# jiffy-neoram-smd.net
KiCad netlist of a schematic drawn in EAGLE
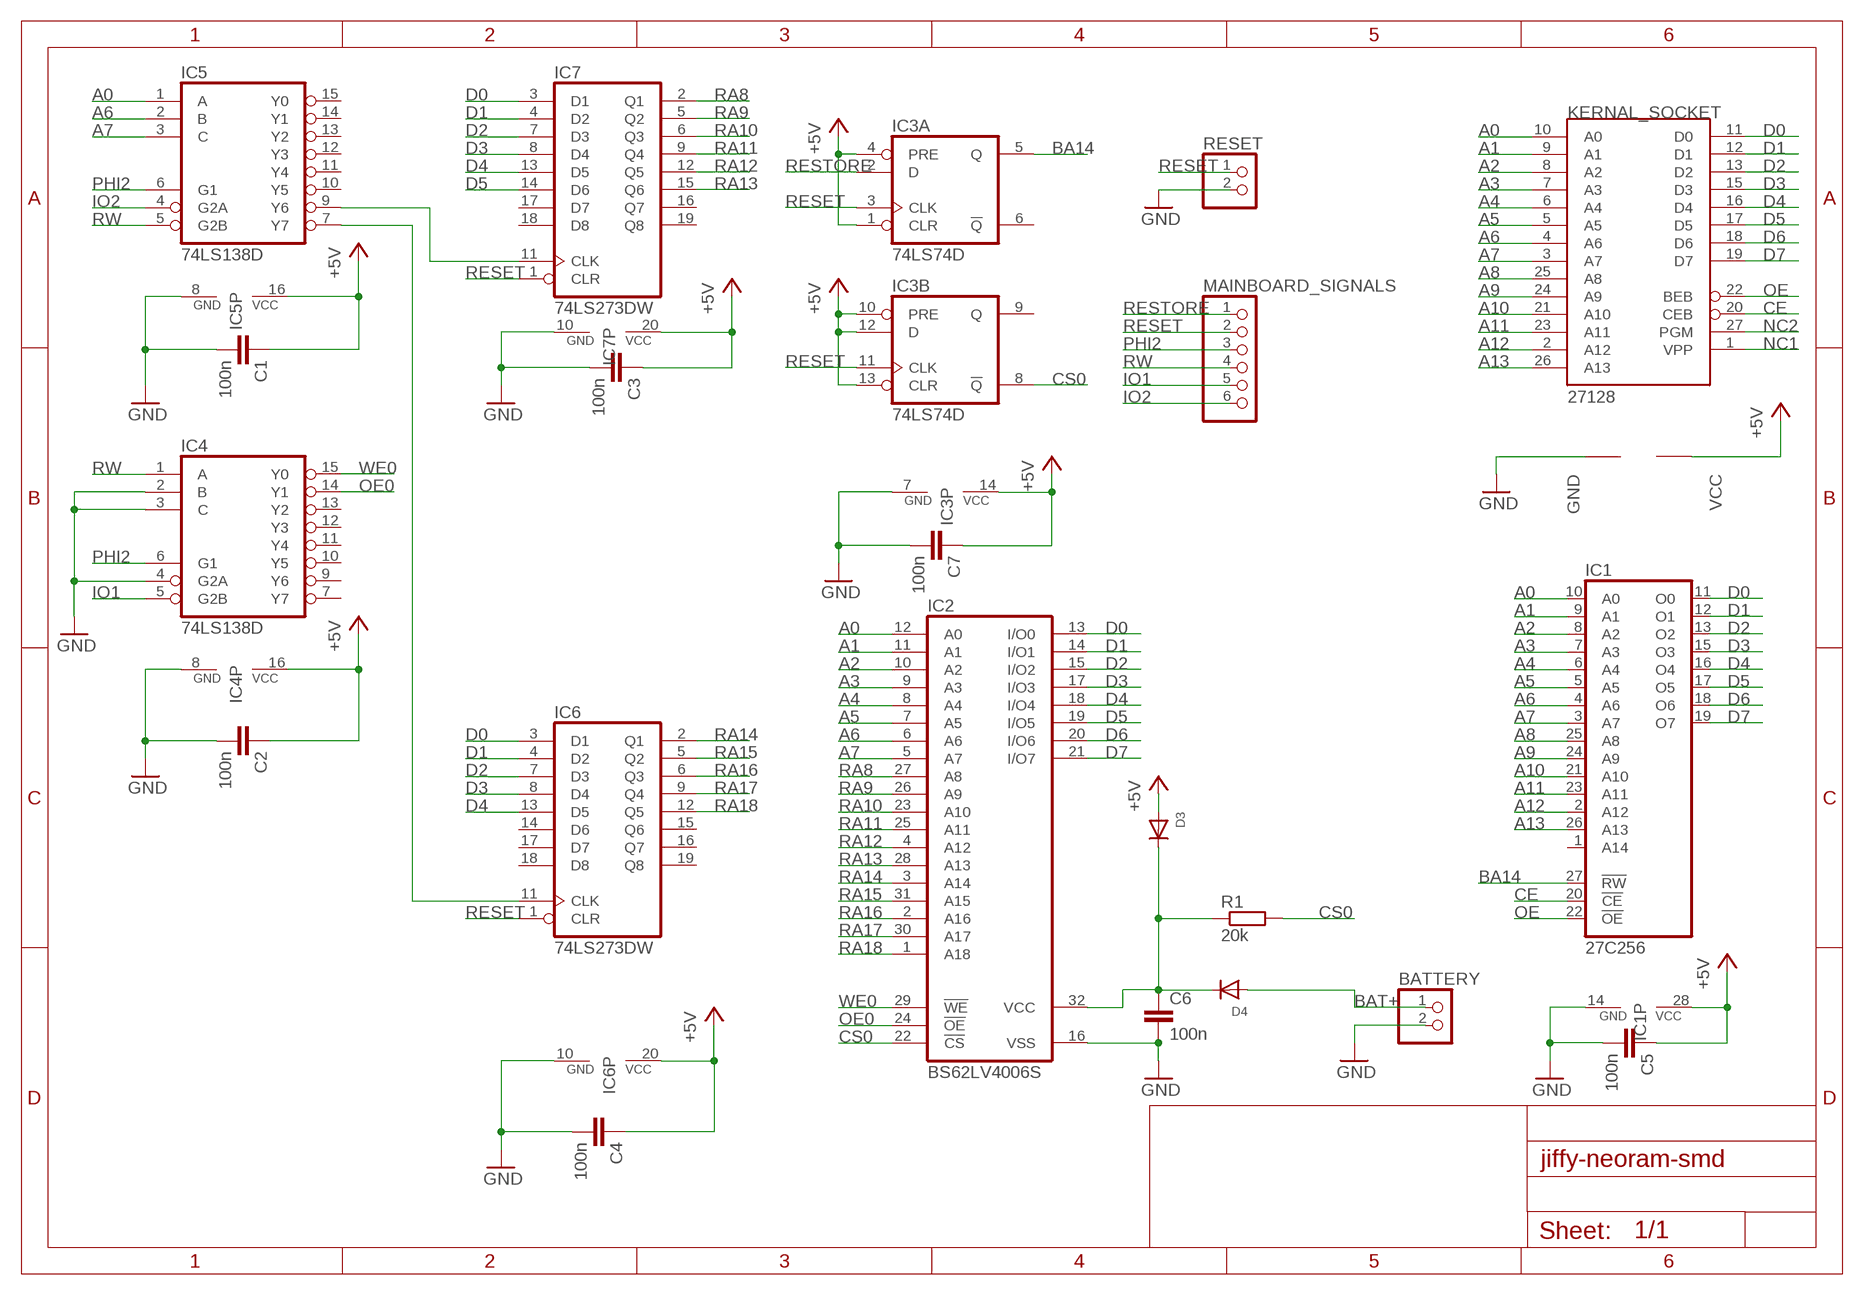
[diagram p0: schematic, sheet 1]

(export (version "E")
  (design (tool "Eeschema 10.0.6"))
  (components
    (comp (ref "BATTERY")
      (value "HEADER-1X2ROUND")
      (footprint "eagle-import:1X02_ROUND")
      (libsource (lib "eagle-import") (part "HEADER-1X2ROUND"))
    )
    (comp (ref "C1")
      (value "100n")
      (footprint "eagle-import:C0603")
      (libsource (lib "eagle-import") (part "C-EUC0603"))
    )
    (comp (ref "C2")
      (value "100n")
      (footprint "eagle-import:C0603")
      (libsource (lib "eagle-import") (part "C-EUC0603"))
    )
    (comp (ref "C3")
      (value "100n")
      (footprint "eagle-import:C0603")
      (libsource (lib "eagle-import") (part "C-EUC0603"))
    )
    (comp (ref "C4")
      (value "100n")
      (footprint "eagle-import:C0603")
      (libsource (lib "eagle-import") (part "C-EUC0603"))
    )
    (comp (ref "C5")
      (value "100n")
      (footprint "eagle-import:C0603")
      (libsource (lib "eagle-import") (part "C-EUC0603"))
    )
    (comp (ref "C6")
      (value "100n")
      (footprint "eagle-import:C0603")
      (libsource (lib "eagle-import") (part "C-EUC0603"))
    )
    (comp (ref "C7")
      (value "100n")
      (footprint "eagle-import:C0603")
      (libsource (lib "eagle-import") (part "C-EUC0603"))
    )
    (comp (ref "D3")
      (value "DIODESOD-323F")
      (footprint "eagle-import:SOD-323F")
      (libsource (lib "eagle-import") (part "DIODESOD-323F"))
    )
    (comp (ref "D4")
      (value "DIODESOD-323F")
      (footprint "eagle-import:SOD-323F")
      (libsource (lib "eagle-import") (part "DIODESOD-323F"))
    )
    (comp (ref "IC1")
      (value "27C256")
      (footprint "eagle-import:DIL28")
      (libsource (lib "eagle-import") (part "TC55257DP"))
    )
    (comp (ref "IC2")
      (value "BS62LV4006S")
      (footprint "eagle-import:SOP-32")
      (libsource (lib "eagle-import") (part "BS62LV4006S"))
    )
    (comp (ref "IC3")
      (value "74LS74D")
      (footprint "eagle-import:SO14")
      (libsource (lib "eagle-import") (part "7474DLS"))
    )
    (comp (ref "IC4")
      (value "74LS138D")
      (footprint "eagle-import:SO16")
      (libsource (lib "eagle-import") (part "74138DLS"))
    )
    (comp (ref "IC5")
      (value "74LS138D")
      (footprint "eagle-import:SO16")
      (libsource (lib "eagle-import") (part "74138DLS"))
    )
    (comp (ref "IC6")
      (value "74LS273DW")
      (footprint "eagle-import:SO20W")
      (libsource (lib "eagle-import") (part "74273DWLS"))
    )
    (comp (ref "IC7")
      (value "74LS273DW")
      (footprint "eagle-import:SO20W")
      (libsource (lib "eagle-import") (part "74273DWLS"))
    )
    (comp (ref "KERNAL_SOCKET")
      (value "OSROM")
      (footprint "eagle-import:DIL28-6")
      (libsource (lib "eagle-import") (part "OSROM"))
    )
    (comp (ref "MAINBOARD_SIGNALS")
      (value "HEADER-1X6ROUND")
      (footprint "eagle-import:1X06_ROUND")
      (libsource (lib "eagle-import") (part "HEADER-1X6ROUND"))
    )
    (comp (ref "R1")
      (value "20k")
      (footprint "eagle-import:R0603")
      (libsource (lib "eagle-import") (part "R-EU_R0603"))
    )
    (comp (ref "RESET")
      (value "HEADER-1X2ROUND")
      (footprint "eagle-import:1X02_ROUND")
      (libsource (lib "eagle-import") (part "HEADER-1X2ROUND"))
    )
  )
  (nets
    (net (code "1") (name "+5V") (class "Default")
      (node (ref "C1") (pin "1") (pinfunction "1_1") (pintype "passive"))
      (node (ref "C2") (pin "1") (pinfunction "1_1") (pintype "passive"))
      (node (ref "C3") (pin "1") (pinfunction "1_1") (pintype "passive"))
      (node (ref "C4") (pin "1") (pinfunction "1_1") (pintype "passive"))
      (node (ref "C5") (pin "1") (pinfunction "1_1") (pintype "passive"))
      (node (ref "C7") (pin "1") (pinfunction "1_1") (pintype "passive"))
      (node (ref "D3") (pin "A") (pinfunction "A_A") (pintype "passive"))
      (node (ref "IC1") (pin "28") (pinfunction "VCC_28") (pintype "power_in"))
      (node (ref "IC3") (pin "1") (pinfunction "CLR_1") (pintype "input"))
      (node (ref "IC3") (pin "10") (pinfunction "PRE_10") (pintype "input"))
      (node (ref "IC3") (pin "12") (pinfunction "D_12") (pintype "input"))
      (node (ref "IC3") (pin "13") (pinfunction "CLR_13") (pintype "input"))
      (node (ref "IC3") (pin "14") (pinfunction "VCC_14") (pintype "power_in"))
      (node (ref "IC3") (pin "4") (pinfunction "PRE_4") (pintype "input"))
      (node (ref "IC4") (pin "16") (pinfunction "VCC_16") (pintype "power_in"))
      (node (ref "IC5") (pin "16") (pinfunction "VCC_16") (pintype "power_in"))
      (node (ref "IC6") (pin "20") (pinfunction "VCC_20") (pintype "power_in"))
      (node (ref "IC7") (pin "20") (pinfunction "VCC_20") (pintype "power_in"))
      (node (ref "KERNAL_SOCKET") (pin "28") (pinfunction "VCC_28") (pintype "power_in"))
    )
    (net (code "2") (name "/A0") (class "Default")
      (node (ref "IC1") (pin "10") (pinfunction "A0_10") (pintype "input"))
      (node (ref "IC2") (pin "12") (pinfunction "A0_12") (pintype "input"))
      (node (ref "IC5") (pin "1") (pinfunction "A_1") (pintype "input"))
      (node (ref "KERNAL_SOCKET") (pin "10") (pinfunction "A0_10") (pintype "input"))
    )
    (net (code "3") (name "/A1") (class "Default")
      (node (ref "IC1") (pin "9") (pinfunction "A1_9") (pintype "input"))
      (node (ref "IC2") (pin "11") (pinfunction "A1_11") (pintype "input"))
      (node (ref "KERNAL_SOCKET") (pin "9") (pinfunction "A1_9") (pintype "input"))
    )
    (net (code "4") (name "/A2") (class "Default")
      (node (ref "IC1") (pin "8") (pinfunction "A2_8") (pintype "input"))
      (node (ref "IC2") (pin "10") (pinfunction "A2_10") (pintype "input"))
      (node (ref "KERNAL_SOCKET") (pin "8") (pinfunction "A2_8") (pintype "input"))
    )
    (net (code "5") (name "/A3") (class "Default")
      (node (ref "IC1") (pin "7") (pinfunction "A3_7") (pintype "input"))
      (node (ref "IC2") (pin "9") (pinfunction "A3_9") (pintype "input"))
      (node (ref "KERNAL_SOCKET") (pin "7") (pinfunction "A3_7") (pintype "input"))
    )
    (net (code "6") (name "/A4") (class "Default")
      (node (ref "IC1") (pin "6") (pinfunction "A4_6") (pintype "input"))
      (node (ref "IC2") (pin "8") (pinfunction "A4_8") (pintype "input"))
      (node (ref "KERNAL_SOCKET") (pin "6") (pinfunction "A4_6") (pintype "input"))
    )
    (net (code "7") (name "/A5") (class "Default")
      (node (ref "IC1") (pin "5") (pinfunction "A5_5") (pintype "input"))
      (node (ref "IC2") (pin "7") (pinfunction "A5_7") (pintype "input"))
      (node (ref "KERNAL_SOCKET") (pin "5") (pinfunction "A5_5") (pintype "input"))
    )
    (net (code "8") (name "/A6") (class "Default")
      (node (ref "IC1") (pin "4") (pinfunction "A6_4") (pintype "input"))
      (node (ref "IC2") (pin "6") (pinfunction "A6_6") (pintype "input"))
      (node (ref "IC5") (pin "2") (pinfunction "B_2") (pintype "input"))
      (node (ref "KERNAL_SOCKET") (pin "4") (pinfunction "A6_4") (pintype "input"))
    )
    (net (code "9") (name "/A7") (class "Default")
      (node (ref "IC1") (pin "3") (pinfunction "A7_3") (pintype "input"))
      (node (ref "IC2") (pin "5") (pinfunction "A7_5") (pintype "input"))
      (node (ref "IC5") (pin "3") (pinfunction "C_3") (pintype "input"))
      (node (ref "KERNAL_SOCKET") (pin "3") (pinfunction "A7_3") (pintype "input"))
    )
    (net (code "10") (name "/A8") (class "Default")
      (node (ref "IC1") (pin "25") (pinfunction "A8_25") (pintype "input"))
      (node (ref "KERNAL_SOCKET") (pin "25") (pinfunction "A8_25") (pintype "input"))
    )
    (net (code "11") (name "/A9") (class "Default")
      (node (ref "IC1") (pin "24") (pinfunction "A9_24") (pintype "input"))
      (node (ref "KERNAL_SOCKET") (pin "24") (pinfunction "A9_24") (pintype "input"))
    )
    (net (code "12") (name "/A10") (class "Default")
      (node (ref "IC1") (pin "21") (pinfunction "A10_21") (pintype "input"))
      (node (ref "KERNAL_SOCKET") (pin "21") (pinfunction "A10_21") (pintype "input"))
    )
    (net (code "13") (name "/A11") (class "Default")
      (node (ref "IC1") (pin "23") (pinfunction "A11_23") (pintype "input"))
      (node (ref "KERNAL_SOCKET") (pin "23") (pinfunction "A11_23") (pintype "input"))
    )
    (net (code "14") (name "/A12") (class "Default")
      (node (ref "IC1") (pin "2") (pinfunction "A12_2") (pintype "input"))
      (node (ref "KERNAL_SOCKET") (pin "2") (pinfunction "A12_2") (pintype "input"))
    )
    (net (code "15") (name "/A13") (class "Default")
      (node (ref "IC1") (pin "26") (pinfunction "A13_26") (pintype "input"))
      (node (ref "KERNAL_SOCKET") (pin "26") (pinfunction "A13_26") (pintype "input"))
    )
    (net (code "16") (name "/BA14") (class "Default")
      (node (ref "IC1") (pin "27") (pinfunction "~{RW}_27") (pintype "input"))
      (node (ref "IC3") (pin "5") (pinfunction "Q_5") (pintype "output"))
    )
    (net (code "17") (name "/BAT+") (class "Default")
      (node (ref "BATTERY") (pin "1") (pinfunction "1_1") (pintype "passive"))
      (node (ref "D4") (pin "A") (pinfunction "A_A") (pintype "passive"))
    )
    (net (code "18") (name "/CE") (class "Default")
      (node (ref "IC1") (pin "20") (pinfunction "~{CE}_20") (pintype "input"))
      (node (ref "KERNAL_SOCKET") (pin "20") (pinfunction "CEB_20") (pintype "input"))
    )
    (net (code "19") (name "/CS0") (class "Default")
      (node (ref "IC2") (pin "22") (pinfunction "~{CS}_22") (pintype "input"))
      (node (ref "IC3") (pin "8") (pinfunction "~{Q}_8") (pintype "output"))
      (node (ref "R1") (pin "2") (pinfunction "2_2") (pintype "passive"))
    )
    (net (code "20") (name "/D0") (class "Default")
      (node (ref "IC1") (pin "11") (pinfunction "O0_11") (pintype "tri_state"))
      (node (ref "IC2") (pin "13") (pinfunction "I/O0_13") (pintype "bidirectional"))
      (node (ref "IC6") (pin "3") (pinfunction "D1_3") (pintype "input"))
      (node (ref "IC7") (pin "3") (pinfunction "D1_3") (pintype "input"))
      (node (ref "KERNAL_SOCKET") (pin "11") (pinfunction "D0_11") (pintype "bidirectional"))
    )
    (net (code "21") (name "/D1") (class "Default")
      (node (ref "IC1") (pin "12") (pinfunction "O1_12") (pintype "tri_state"))
      (node (ref "IC2") (pin "14") (pinfunction "I/O1_14") (pintype "bidirectional"))
      (node (ref "IC6") (pin "4") (pinfunction "D2_4") (pintype "input"))
      (node (ref "IC7") (pin "4") (pinfunction "D2_4") (pintype "input"))
      (node (ref "KERNAL_SOCKET") (pin "12") (pinfunction "D1_12") (pintype "bidirectional"))
    )
    (net (code "22") (name "/D2") (class "Default")
      (node (ref "IC1") (pin "13") (pinfunction "O2_13") (pintype "tri_state"))
      (node (ref "IC2") (pin "15") (pinfunction "I/O2_15") (pintype "bidirectional"))
      (node (ref "IC6") (pin "7") (pinfunction "D3_7") (pintype "input"))
      (node (ref "IC7") (pin "7") (pinfunction "D3_7") (pintype "input"))
      (node (ref "KERNAL_SOCKET") (pin "13") (pinfunction "D2_13") (pintype "bidirectional"))
    )
    (net (code "23") (name "/D3") (class "Default")
      (node (ref "IC1") (pin "15") (pinfunction "O3_15") (pintype "tri_state"))
      (node (ref "IC2") (pin "17") (pinfunction "I/O3_17") (pintype "bidirectional"))
      (node (ref "IC6") (pin "8") (pinfunction "D4_8") (pintype "input"))
      (node (ref "IC7") (pin "8") (pinfunction "D4_8") (pintype "input"))
      (node (ref "KERNAL_SOCKET") (pin "15") (pinfunction "D3_15") (pintype "bidirectional"))
    )
    (net (code "24") (name "/D4") (class "Default")
      (node (ref "IC1") (pin "16") (pinfunction "O4_16") (pintype "tri_state"))
      (node (ref "IC2") (pin "18") (pinfunction "I/O4_18") (pintype "bidirectional"))
      (node (ref "IC6") (pin "13") (pinfunction "D5_13") (pintype "input"))
      (node (ref "IC7") (pin "13") (pinfunction "D5_13") (pintype "input"))
      (node (ref "KERNAL_SOCKET") (pin "16") (pinfunction "D4_16") (pintype "bidirectional"))
    )
    (net (code "25") (name "/D5") (class "Default")
      (node (ref "IC1") (pin "17") (pinfunction "O5_17") (pintype "tri_state"))
      (node (ref "IC2") (pin "19") (pinfunction "I/O5_19") (pintype "bidirectional"))
      (node (ref "IC7") (pin "14") (pinfunction "D6_14") (pintype "input"))
      (node (ref "KERNAL_SOCKET") (pin "17") (pinfunction "D5_17") (pintype "bidirectional"))
    )
    (net (code "26") (name "/D6") (class "Default")
      (node (ref "IC1") (pin "18") (pinfunction "O6_18") (pintype "tri_state"))
      (node (ref "IC2") (pin "20") (pinfunction "I/O6_20") (pintype "bidirectional"))
      (node (ref "KERNAL_SOCKET") (pin "18") (pinfunction "D6_18") (pintype "bidirectional"))
    )
    (net (code "27") (name "/D7") (class "Default")
      (node (ref "IC1") (pin "19") (pinfunction "O7_19") (pintype "tri_state"))
      (node (ref "IC2") (pin "21") (pinfunction "I/O7_21") (pintype "bidirectional"))
      (node (ref "KERNAL_SOCKET") (pin "19") (pinfunction "D7_19") (pintype "bidirectional"))
    )
    (net (code "28") (name "/IO1") (class "Default")
      (node (ref "IC4") (pin "5") (pinfunction "G2B_5") (pintype "input"))
      (node (ref "MAINBOARD_SIGNALS") (pin "5") (pinfunction "5_5") (pintype "passive"))
    )
    (net (code "29") (name "/IO2") (class "Default")
      (node (ref "IC5") (pin "4") (pinfunction "G2A_4") (pintype "input"))
      (node (ref "MAINBOARD_SIGNALS") (pin "6") (pinfunction "6_6") (pintype "passive"))
    )
    (net (code "30") (name "/NC1") (class "Default")
      (node (ref "KERNAL_SOCKET") (pin "1") (pinfunction "VPP_1") (pintype "power_in"))
    )
    (net (code "31") (name "/NC2") (class "Default")
      (node (ref "KERNAL_SOCKET") (pin "27") (pinfunction "PGM_27") (pintype "input"))
    )
    (net (code "32") (name "/OE") (class "Default")
      (node (ref "IC1") (pin "22") (pinfunction "~{OE}_22") (pintype "input"))
      (node (ref "KERNAL_SOCKET") (pin "22") (pinfunction "BEB_22") (pintype "input"))
    )
    (net (code "33") (name "/OE0") (class "Default")
      (node (ref "IC2") (pin "24") (pinfunction "~{OE}_24") (pintype "input"))
      (node (ref "IC4") (pin "14") (pinfunction "Y1_14") (pintype "output"))
    )
    (net (code "34") (name "/PHI2") (class "Default")
      (node (ref "IC4") (pin "6") (pinfunction "G1_6") (pintype "input"))
      (node (ref "IC5") (pin "6") (pinfunction "G1_6") (pintype "input"))
      (node (ref "MAINBOARD_SIGNALS") (pin "3") (pinfunction "3_3") (pintype "passive"))
    )
    (net (code "35") (name "/RA8") (class "Default")
      (node (ref "IC2") (pin "27") (pinfunction "A8_27") (pintype "input"))
      (node (ref "IC7") (pin "2") (pinfunction "Q1_2") (pintype "output"))
    )
    (net (code "36") (name "/RA9") (class "Default")
      (node (ref "IC2") (pin "26") (pinfunction "A9_26") (pintype "input"))
      (node (ref "IC7") (pin "5") (pinfunction "Q2_5") (pintype "output"))
    )
    (net (code "37") (name "/RA10") (class "Default")
      (node (ref "IC2") (pin "23") (pinfunction "A10_23") (pintype "input"))
      (node (ref "IC7") (pin "6") (pinfunction "Q3_6") (pintype "output"))
    )
    (net (code "38") (name "/RA11") (class "Default")
      (node (ref "IC2") (pin "25") (pinfunction "A11_25") (pintype "input"))
      (node (ref "IC7") (pin "9") (pinfunction "Q4_9") (pintype "output"))
    )
    (net (code "39") (name "/RA12") (class "Default")
      (node (ref "IC2") (pin "4") (pinfunction "A12_4") (pintype "input"))
      (node (ref "IC7") (pin "12") (pinfunction "Q5_12") (pintype "output"))
    )
    (net (code "40") (name "/RA13") (class "Default")
      (node (ref "IC2") (pin "28") (pinfunction "A13_28") (pintype "input"))
      (node (ref "IC7") (pin "15") (pinfunction "Q6_15") (pintype "output"))
    )
    (net (code "41") (name "/RA14") (class "Default")
      (node (ref "IC2") (pin "3") (pinfunction "A14_3") (pintype "input"))
      (node (ref "IC6") (pin "2") (pinfunction "Q1_2") (pintype "output"))
    )
    (net (code "42") (name "/RA15") (class "Default")
      (node (ref "IC2") (pin "31") (pinfunction "A15_31") (pintype "input"))
      (node (ref "IC6") (pin "5") (pinfunction "Q2_5") (pintype "output"))
    )
    (net (code "43") (name "/RA16") (class "Default")
      (node (ref "IC2") (pin "2") (pinfunction "A16_2") (pintype "input"))
      (node (ref "IC6") (pin "6") (pinfunction "Q3_6") (pintype "output"))
    )
    (net (code "44") (name "/RA17") (class "Default")
      (node (ref "IC2") (pin "30") (pinfunction "A17_30") (pintype "input"))
      (node (ref "IC6") (pin "9") (pinfunction "Q4_9") (pintype "output"))
    )
    (net (code "45") (name "/RA18") (class "Default")
      (node (ref "IC2") (pin "1") (pinfunction "A18_1") (pintype "input"))
      (node (ref "IC6") (pin "12") (pinfunction "Q5_12") (pintype "output"))
    )
    (net (code "46") (name "/RESET") (class "Default")
      (node (ref "IC3") (pin "11") (pinfunction "CLK_11") (pintype "input"))
      (node (ref "IC3") (pin "3") (pinfunction "CLK_3") (pintype "input"))
      (node (ref "IC6") (pin "1") (pinfunction "CLR_1") (pintype "input"))
      (node (ref "IC7") (pin "1") (pinfunction "CLR_1") (pintype "input"))
      (node (ref "MAINBOARD_SIGNALS") (pin "2") (pinfunction "2_2") (pintype "passive"))
      (node (ref "RESET") (pin "1") (pinfunction "1_1") (pintype "passive"))
    )
    (net (code "47") (name "/RESTORE") (class "Default")
      (node (ref "IC3") (pin "2") (pinfunction "D_2") (pintype "input"))
      (node (ref "MAINBOARD_SIGNALS") (pin "1") (pinfunction "1_1") (pintype "passive"))
    )
    (net (code "48") (name "/RW") (class "Default")
      (node (ref "IC4") (pin "1") (pinfunction "A_1") (pintype "input"))
      (node (ref "IC5") (pin "5") (pinfunction "G2B_5") (pintype "input"))
      (node (ref "MAINBOARD_SIGNALS") (pin "4") (pinfunction "4_4") (pintype "passive"))
    )
    (net (code "49") (name "/WE0") (class "Default")
      (node (ref "IC2") (pin "29") (pinfunction "~{WE}_29") (pintype "input"))
      (node (ref "IC4") (pin "15") (pinfunction "Y0_15") (pintype "output"))
    )
    (net (code "50") (name "GND") (class "Default")
      (node (ref "BATTERY") (pin "2") (pinfunction "2_2") (pintype "passive"))
      (node (ref "C1") (pin "2") (pinfunction "2_2") (pintype "passive"))
      (node (ref "C2") (pin "2") (pinfunction "2_2") (pintype "passive"))
      (node (ref "C3") (pin "2") (pinfunction "2_2") (pintype "passive"))
      (node (ref "C4") (pin "2") (pinfunction "2_2") (pintype "passive"))
      (node (ref "C5") (pin "2") (pinfunction "2_2") (pintype "passive"))
      (node (ref "C6") (pin "2") (pinfunction "2_2") (pintype "passive"))
      (node (ref "C7") (pin "2") (pinfunction "2_2") (pintype "passive"))
      (node (ref "IC1") (pin "14") (pinfunction "GND_14") (pintype "power_in"))
      (node (ref "IC2") (pin "16") (pinfunction "VSS_16") (pintype "power_in"))
      (node (ref "IC3") (pin "7") (pinfunction "GND_7") (pintype "power_in"))
      (node (ref "IC4") (pin "2") (pinfunction "B_2") (pintype "input"))
      (node (ref "IC4") (pin "3") (pinfunction "C_3") (pintype "input"))
      (node (ref "IC4") (pin "4") (pinfunction "G2A_4") (pintype "input"))
      (node (ref "IC4") (pin "8") (pinfunction "GND_8") (pintype "power_in"))
      (node (ref "IC5") (pin "8") (pinfunction "GND_8") (pintype "power_in"))
      (node (ref "IC6") (pin "10") (pinfunction "GND_10") (pintype "power_in"))
      (node (ref "IC7") (pin "10") (pinfunction "GND_10") (pintype "power_in"))
      (node (ref "KERNAL_SOCKET") (pin "14") (pinfunction "GND_14") (pintype "power_in"))
      (node (ref "RESET") (pin "2") (pinfunction "2_2") (pintype "passive"))
    )
    (net (code "51") (name "Net-(IC2-VCC)") (class "Default")
      (node (ref "C6") (pin "1") (pinfunction "1_1") (pintype "passive"))
      (node (ref "D3") (pin "C") (pinfunction "C_C") (pintype "passive"))
      (node (ref "D4") (pin "C") (pinfunction "C_C") (pintype "passive"))
      (node (ref "IC2") (pin "32") (pinfunction "VCC_32") (pintype "power_in"))
      (node (ref "R1") (pin "1") (pinfunction "1_1") (pintype "passive"))
    )
    (net (code "52") (name "Net-(IC5A-Y6)") (class "Default")
      (node (ref "IC5") (pin "9") (pinfunction "Y6_9") (pintype "output"))
      (node (ref "IC7") (pin "11") (pinfunction "CLK_11") (pintype "input"))
    )
    (net (code "53") (name "Net-(IC5A-Y7)") (class "Default")
      (node (ref "IC5") (pin "7") (pinfunction "Y7_7") (pintype "output"))
      (node (ref "IC6") (pin "11") (pinfunction "CLK_11") (pintype "input"))
    )
    (net (code "54") (name "unconnected-(IC1A-A14-Pad1)") (class "Default")
      (node (ref "IC1") (pin "1") (pinfunction "A14_1") (pintype "input"))
    )
    (net (code "55") (name "unconnected-(IC3A-~{Q}-Pad6)") (class "Default")
      (node (ref "IC3") (pin "6") (pinfunction "~{Q}_6") (pintype "output"))
    )
    (net (code "56") (name "unconnected-(IC3B-Q-Pad9)") (class "Default")
      (node (ref "IC3") (pin "9") (pinfunction "Q_9") (pintype "output"))
    )
    (net (code "57") (name "unconnected-(IC4A-Y2-Pad13)") (class "Default")
      (node (ref "IC4") (pin "13") (pinfunction "Y2_13") (pintype "output"))
    )
    (net (code "58") (name "unconnected-(IC4A-Y3-Pad12)") (class "Default")
      (node (ref "IC4") (pin "12") (pinfunction "Y3_12") (pintype "output"))
    )
    (net (code "59") (name "unconnected-(IC4A-Y4-Pad11)") (class "Default")
      (node (ref "IC4") (pin "11") (pinfunction "Y4_11") (pintype "output"))
    )
    (net (code "60") (name "unconnected-(IC4A-Y5-Pad10)") (class "Default")
      (node (ref "IC4") (pin "10") (pinfunction "Y5_10") (pintype "output"))
    )
    (net (code "61") (name "unconnected-(IC4A-Y6-Pad9)") (class "Default")
      (node (ref "IC4") (pin "9") (pinfunction "Y6_9") (pintype "output"))
    )
    (net (code "62") (name "unconnected-(IC4A-Y7-Pad7)") (class "Default")
      (node (ref "IC4") (pin "7") (pinfunction "Y7_7") (pintype "output"))
    )
    (net (code "63") (name "unconnected-(IC5A-Y0-Pad15)") (class "Default")
      (node (ref "IC5") (pin "15") (pinfunction "Y0_15") (pintype "output"))
    )
    (net (code "64") (name "unconnected-(IC5A-Y1-Pad14)") (class "Default")
      (node (ref "IC5") (pin "14") (pinfunction "Y1_14") (pintype "output"))
    )
    (net (code "65") (name "unconnected-(IC5A-Y2-Pad13)") (class "Default")
      (node (ref "IC5") (pin "13") (pinfunction "Y2_13") (pintype "output"))
    )
    (net (code "66") (name "unconnected-(IC5A-Y3-Pad12)") (class "Default")
      (node (ref "IC5") (pin "12") (pinfunction "Y3_12") (pintype "output"))
    )
    (net (code "67") (name "unconnected-(IC5A-Y4-Pad11)") (class "Default")
      (node (ref "IC5") (pin "11") (pinfunction "Y4_11") (pintype "output"))
    )
    (net (code "68") (name "unconnected-(IC5A-Y5-Pad10)") (class "Default")
      (node (ref "IC5") (pin "10") (pinfunction "Y5_10") (pintype "output"))
    )
    (net (code "69") (name "unconnected-(IC6A-D6-Pad14)") (class "Default")
      (node (ref "IC6") (pin "14") (pinfunction "D6_14") (pintype "input"))
    )
    (net (code "70") (name "unconnected-(IC6A-D7-Pad17)") (class "Default")
      (node (ref "IC6") (pin "17") (pinfunction "D7_17") (pintype "input"))
    )
    (net (code "71") (name "unconnected-(IC6A-D8-Pad18)") (class "Default")
      (node (ref "IC6") (pin "18") (pinfunction "D8_18") (pintype "input"))
    )
    (net (code "72") (name "unconnected-(IC6A-Q6-Pad15)") (class "Default")
      (node (ref "IC6") (pin "15") (pinfunction "Q6_15") (pintype "output"))
    )
    (net (code "73") (name "unconnected-(IC6A-Q7-Pad16)") (class "Default")
      (node (ref "IC6") (pin "16") (pinfunction "Q7_16") (pintype "output"))
    )
    (net (code "74") (name "unconnected-(IC6A-Q8-Pad19)") (class "Default")
      (node (ref "IC6") (pin "19") (pinfunction "Q8_19") (pintype "output"))
    )
    (net (code "75") (name "unconnected-(IC7A-D7-Pad17)") (class "Default")
      (node (ref "IC7") (pin "17") (pinfunction "D7_17") (pintype "input"))
    )
    (net (code "76") (name "unconnected-(IC7A-D8-Pad18)") (class "Default")
      (node (ref "IC7") (pin "18") (pinfunction "D8_18") (pintype "input"))
    )
    (net (code "77") (name "unconnected-(IC7A-Q7-Pad16)") (class "Default")
      (node (ref "IC7") (pin "16") (pinfunction "Q7_16") (pintype "output"))
    )
    (net (code "78") (name "unconnected-(IC7A-Q8-Pad19)") (class "Default")
      (node (ref "IC7") (pin "19") (pinfunction "Q8_19") (pintype "output"))
    )
  )
)
